# Bluetooth.net
KiCad netlist of a schematic drawn in Altium Designer
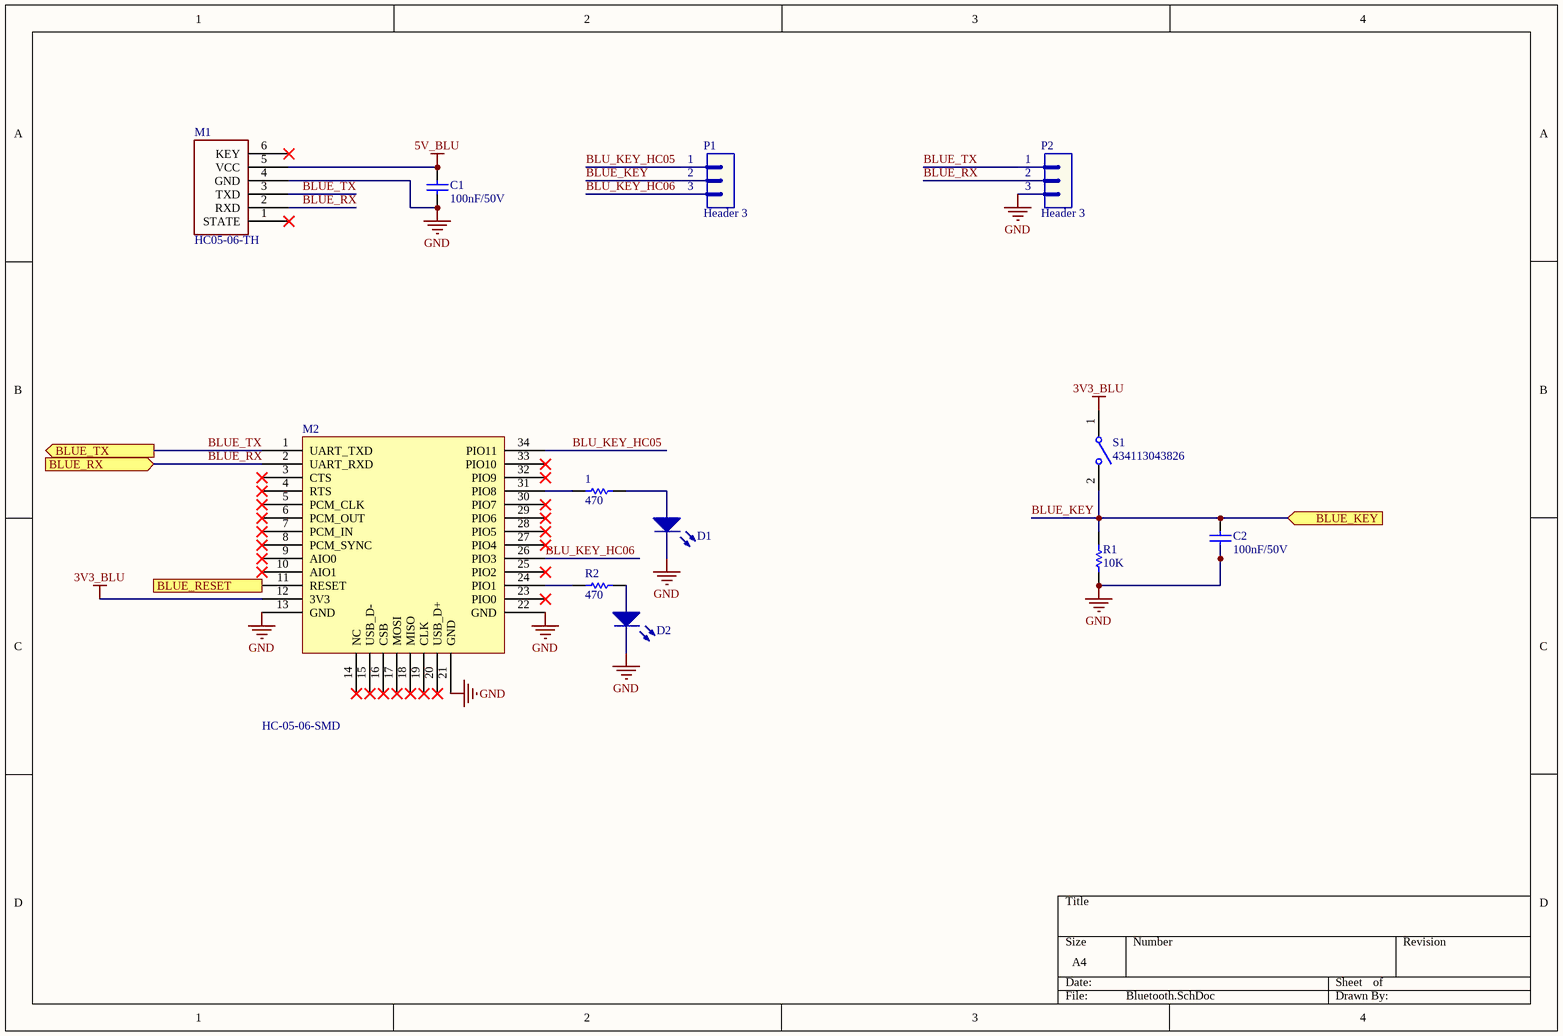
[diagram p0: Bluetooth.SchDoc]

(export (version "E")
  (design (tool "Eeschema 10.0.6"))
  (components
    (comp (ref "1")
      (value "470")
      (footprint "Resistor:RES-SM-0805")
      (description "RES 1K OHM 1% 1/4W 0805")
      (fields
        (field (name "MANUFACTURER") "Stackpole Electronics Inc")
        (field (name "MANUFACTURER PART NUMBER") "RNCP0805FTD1K00")
      )
      (libsource (lib "Resistor") (part "Res-1K-0805"))
    )
    (comp (ref "C1")
      (value "100nF/50V")
      (footprint "CAP-SM-0805")
      (description "CAP CER 1000PF 100V X7R 0805")
      (fields
        (field (name "MANUFACTURER") "Johanson Dielectrics Inc.")
        (field (name "MANUFACTURER PART NUMBER") "101X15W102MV4E")
      )
      (libsource (lib "Capacitor") (part "Cap-1nF-50V-0805"))
    )
    (comp (ref "C2")
      (value "100nF/50V")
      (footprint "CAP-SM-0805")
      (description "CAP CER 1000PF 100V X7R 0805")
      (fields
        (field (name "MANUFACTURER") "Johanson Dielectrics Inc.")
        (field (name "MANUFACTURER PART NUMBER") "101X15W102MV4E")
      )
      (libsource (lib "Capacitor") (part "Cap-1nF-50V-0805"))
    )
    (comp (ref "D1") (value "LED") (footprint "LED_0603_Blue") (libsource (lib "PIF_C16_lib") (part "LED")))
    (comp (ref "D2") (value "LED") (footprint "LED_0603_Blue") (libsource (lib "PIF_C16_lib") (part "LED")))
    (comp (ref "M1")
      (value "HC05-06-TH")
      (footprint "HC-05-06-TH")
      (libsource (lib "Schlib1") (part "HC05-06-TH"))
    )
    (comp (ref "M2")
      (value "HC-05-06-SMD")
      (footprint "HC-05-06-SMD")
      (libsource (lib "Integrated_Library_Test") (part "HC-05-06-SMD"))
    )
    (comp (ref "P1")
      (value "Header 3")
      (footprint "JP3")
      (description "Header, 3-Pin")
      (fields (field (name "PUBLISHER") "Altium Limited"))
      (libsource (lib "PIF_C16_lib") (part "Header 3"))
    )
    (comp (ref "P2")
      (value "Header 3")
      (footprint "JP3")
      (description "Header, 3-Pin")
      (fields (field (name "PUBLISHER") "Altium Limited"))
      (libsource (lib "PIF_C16_lib") (part "Header 3"))
    )
    (comp (ref "R1")
      (value "10K")
      (footprint "Resistor:RES-SM-0805")
      (description "RES 0 OHM JUMPER 0805")
      (fields
        (field (name "MANUFACTURER") "Vishay Dale")
        (field (name "MANUFACTURER PART NUMBER") "WSL080500000ZEA9")
      )
      (libsource (lib "Resistor") (part "Res-0-0805"))
    )
    (comp (ref "R2")
      (value "470")
      (footprint "Resistor:RES-SM-0805")
      (description "RES 1K OHM 1% 1/4W 0805")
      (fields
        (field (name "MANUFACTURER") "Stackpole Electronics Inc")
        (field (name "MANUFACTURER PART NUMBER") "RNCP0805FTD1K00")
      )
      (libsource (lib "Resistor") (part "Res-1K-0805"))
    )
    (comp (ref "S1")
      (value "434113043826")
      (footprint "434113043826")
      (description "WS-TASV J-Bend SMT Tact Switch 6x3.5mm, height 4.3mm, 260gf")
      (fields (field (name "PUBLISHER") "Wurth Elektronik"))
      (libsource (lib "434113043826_Altium_WS-TASV_rev20a") (part "434113043826"))
    )
  )
  (nets
    (net (code "1") (name "/BLUE_KEY") (class "Default")
      (node (ref "C2") (pin "2") (pinfunction "2_2") (pintype "passive"))
      (node (ref "P1") (pin "2") (pinfunction "2_2") (pintype "passive"))
      (node (ref "R1") (pin "1") (pinfunction "1_1") (pintype "passive"))
      (node (ref "S1") (pin "2") (pinfunction "2_2") (pintype "passive"))
    )
    (net (code "2") (name "/BLUE_RESET") (class "Default")
      (node (ref "M2") (pin "11") (pinfunction "RESET_11") (pintype "passive"))
    )
    (net (code "3") (name "/BLUE_RX") (class "Default")
      (node (ref "M1") (pin "2") (pinfunction "RXD_2") (pintype "passive"))
      (node (ref "M2") (pin "2") (pinfunction "UART_RXD_2") (pintype "passive"))
      (node (ref "P2") (pin "2") (pinfunction "2_2") (pintype "passive"))
    )
    (net (code "4") (name "/BLUE_TX") (class "Default")
      (node (ref "M1") (pin "3") (pinfunction "TXD_3") (pintype "passive"))
      (node (ref "M2") (pin "1") (pinfunction "UART_TXD_1") (pintype "passive"))
      (node (ref "P2") (pin "1") (pinfunction "1_1") (pintype "passive"))
    )
    (net (code "5") (name "/BLU_KEY_HC05") (class "Default")
      (node (ref "M2") (pin "34") (pinfunction "PIO11_34") (pintype "passive"))
      (node (ref "P1") (pin "1") (pinfunction "1_1") (pintype "passive"))
    )
    (net (code "6") (name "/BLU_KEY_HC06") (class "Default")
      (node (ref "M2") (pin "26") (pinfunction "PIO3_26") (pintype "passive"))
      (node (ref "P1") (pin "3") (pinfunction "3_3") (pintype "passive"))
    )
    (net (code "7") (name "3V3_BLU") (class "Default")
      (node (ref "M2") (pin "12") (pinfunction "3V3_12") (pintype "passive"))
      (node (ref "S1") (pin "1") (pinfunction "1_1") (pintype "passive"))
    )
    (net (code "8") (name "5V_BLU") (class "Default")
      (node (ref "C1") (pin "2") (pinfunction "2_2") (pintype "passive"))
      (node (ref "M1") (pin "5") (pinfunction "VCC_5") (pintype "passive"))
    )
    (net (code "9") (name "GND") (class "Default")
      (node (ref "C1") (pin "1") (pinfunction "1_1") (pintype "passive"))
      (node (ref "C2") (pin "1") (pinfunction "1_1") (pintype "passive"))
      (node (ref "D1") (pin "2") (pinfunction "K_2") (pintype "passive"))
      (node (ref "D2") (pin "2") (pinfunction "K_2") (pintype "passive"))
      (node (ref "M1") (pin "4") (pinfunction "GND_4") (pintype "passive"))
      (node (ref "M2") (pin "13") (pinfunction "GND_13") (pintype "passive"))
      (node (ref "M2") (pin "21") (pinfunction "GND_21") (pintype "passive"))
      (node (ref "M2") (pin "22") (pinfunction "GND_22") (pintype "passive"))
      (node (ref "P2") (pin "3") (pinfunction "3_3") (pintype "passive"))
      (node (ref "R1") (pin "2") (pinfunction "2_2") (pintype "passive"))
    )
    (net (code "10") (name "Net-(D1-A)") (class "Default")
      (node (ref "1") (pin "2") (pinfunction "2_2") (pintype "passive"))
      (node (ref "D1") (pin "1") (pinfunction "A_1") (pintype "passive"))
    )
    (net (code "11") (name "Net-(D2-A)") (class "Default")
      (node (ref "D2") (pin "1") (pinfunction "A_1") (pintype "passive"))
      (node (ref "R2") (pin "2") (pinfunction "2_2") (pintype "passive"))
    )
    (net (code "12") (name "Net-(M2-PIO1)") (class "Default")
      (node (ref "M2") (pin "24") (pinfunction "PIO1_24") (pintype "passive"))
      (node (ref "R2") (pin "1") (pinfunction "1_1") (pintype "passive"))
    )
    (net (code "13") (name "Net-(M2-PIO8)") (class "Default")
      (node (ref "1") (pin "1") (pinfunction "1_1") (pintype "passive"))
      (node (ref "M2") (pin "31") (pinfunction "PIO8_31") (pintype "passive"))
    )
    (net (code "14") (name "unconnected-(M1-KEY-Pad6)") (class "Default")
      (node (ref "M1") (pin "6") (pinfunction "KEY_6") (pintype "passive+no_connect"))
    )
    (net (code "15") (name "unconnected-(M1-STATE-Pad1)") (class "Default")
      (node (ref "M1") (pin "1") (pinfunction "STATE_1") (pintype "passive+no_connect"))
    )
    (net (code "16") (name "unconnected-(M2-AIO0-Pad9)") (class "Default")
      (node (ref "M2") (pin "9") (pinfunction "AIO0_9") (pintype "passive+no_connect"))
    )
    (net (code "17") (name "unconnected-(M2-AIO1-Pad10)") (class "Default")
      (node (ref "M2") (pin "10") (pinfunction "AIO1_10") (pintype "passive+no_connect"))
    )
    (net (code "18") (name "unconnected-(M2-CLK-Pad19)") (class "Default")
      (node (ref "M2") (pin "19") (pinfunction "CLK_19") (pintype "passive+no_connect"))
    )
    (net (code "19") (name "unconnected-(M2-CSB-Pad16)") (class "Default")
      (node (ref "M2") (pin "16") (pinfunction "CSB_16") (pintype "passive+no_connect"))
    )
    (net (code "20") (name "unconnected-(M2-CTS-Pad3)") (class "Default")
      (node (ref "M2") (pin "3") (pinfunction "CTS_3") (pintype "passive+no_connect"))
    )
    (net (code "21") (name "unconnected-(M2-MISO-Pad18)") (class "Default")
      (node (ref "M2") (pin "18") (pinfunction "MISO_18") (pintype "passive+no_connect"))
    )
    (net (code "22") (name "unconnected-(M2-MOSI-Pad17)") (class "Default")
      (node (ref "M2") (pin "17") (pinfunction "MOSI_17") (pintype "passive+no_connect"))
    )
    (net (code "23") (name "unconnected-(M2-NC-Pad14)") (class "Default")
      (node (ref "M2") (pin "14") (pinfunction "NC_14") (pintype "passive+no_connect"))
    )
    (net (code "24") (name "unconnected-(M2-PCM_CLK-Pad5)") (class "Default")
      (node (ref "M2") (pin "5") (pinfunction "PCM_CLK_5") (pintype "passive+no_connect"))
    )
    (net (code "25") (name "unconnected-(M2-PCM_IN-Pad7)") (class "Default")
      (node (ref "M2") (pin "7") (pinfunction "PCM_IN_7") (pintype "passive+no_connect"))
    )
    (net (code "26") (name "unconnected-(M2-PCM_OUT-Pad6)") (class "Default")
      (node (ref "M2") (pin "6") (pinfunction "PCM_OUT_6") (pintype "passive+no_connect"))
    )
    (net (code "27") (name "unconnected-(M2-PCM_SYNC-Pad8)") (class "Default")
      (node (ref "M2") (pin "8") (pinfunction "PCM_SYNC_8") (pintype "passive+no_connect"))
    )
    (net (code "28") (name "unconnected-(M2-PIO0-Pad23)") (class "Default")
      (node (ref "M2") (pin "23") (pinfunction "PIO0_23") (pintype "passive+no_connect"))
    )
    (net (code "29") (name "unconnected-(M2-PIO2-Pad25)") (class "Default")
      (node (ref "M2") (pin "25") (pinfunction "PIO2_25") (pintype "passive+no_connect"))
    )
    (net (code "30") (name "unconnected-(M2-PIO4-Pad27)") (class "Default")
      (node (ref "M2") (pin "27") (pinfunction "PIO4_27") (pintype "passive+no_connect"))
    )
    (net (code "31") (name "unconnected-(M2-PIO5-Pad28)") (class "Default")
      (node (ref "M2") (pin "28") (pinfunction "PIO5_28") (pintype "passive+no_connect"))
    )
    (net (code "32") (name "unconnected-(M2-PIO6-Pad29)") (class "Default")
      (node (ref "M2") (pin "29") (pinfunction "PIO6_29") (pintype "passive+no_connect"))
    )
    (net (code "33") (name "unconnected-(M2-PIO7-Pad30)") (class "Default")
      (node (ref "M2") (pin "30") (pinfunction "PIO7_30") (pintype "passive+no_connect"))
    )
    (net (code "34") (name "unconnected-(M2-PIO9-Pad32)") (class "Default")
      (node (ref "M2") (pin "32") (pinfunction "PIO9_32") (pintype "passive+no_connect"))
    )
    (net (code "35") (name "unconnected-(M2-PIO10-Pad33)") (class "Default")
      (node (ref "M2") (pin "33") (pinfunction "PIO10_33") (pintype "passive+no_connect"))
    )
    (net (code "36") (name "unconnected-(M2-RTS-Pad4)") (class "Default")
      (node (ref "M2") (pin "4") (pinfunction "RTS_4") (pintype "passive+no_connect"))
    )
    (net (code "37") (name "unconnected-(M2-USB_D+-Pad20)") (class "Default")
      (node (ref "M2") (pin "20") (pinfunction "USB_D+_20") (pintype "passive+no_connect"))
    )
    (net (code "38") (name "unconnected-(M2-USB_D--Pad15)") (class "Default")
      (node (ref "M2") (pin "15") (pinfunction "USB_D-_15") (pintype "passive+no_connect"))
    )
  )
)
